# LCD_SCH.net
KiCad netlist of a schematic drawn in Altium Designer
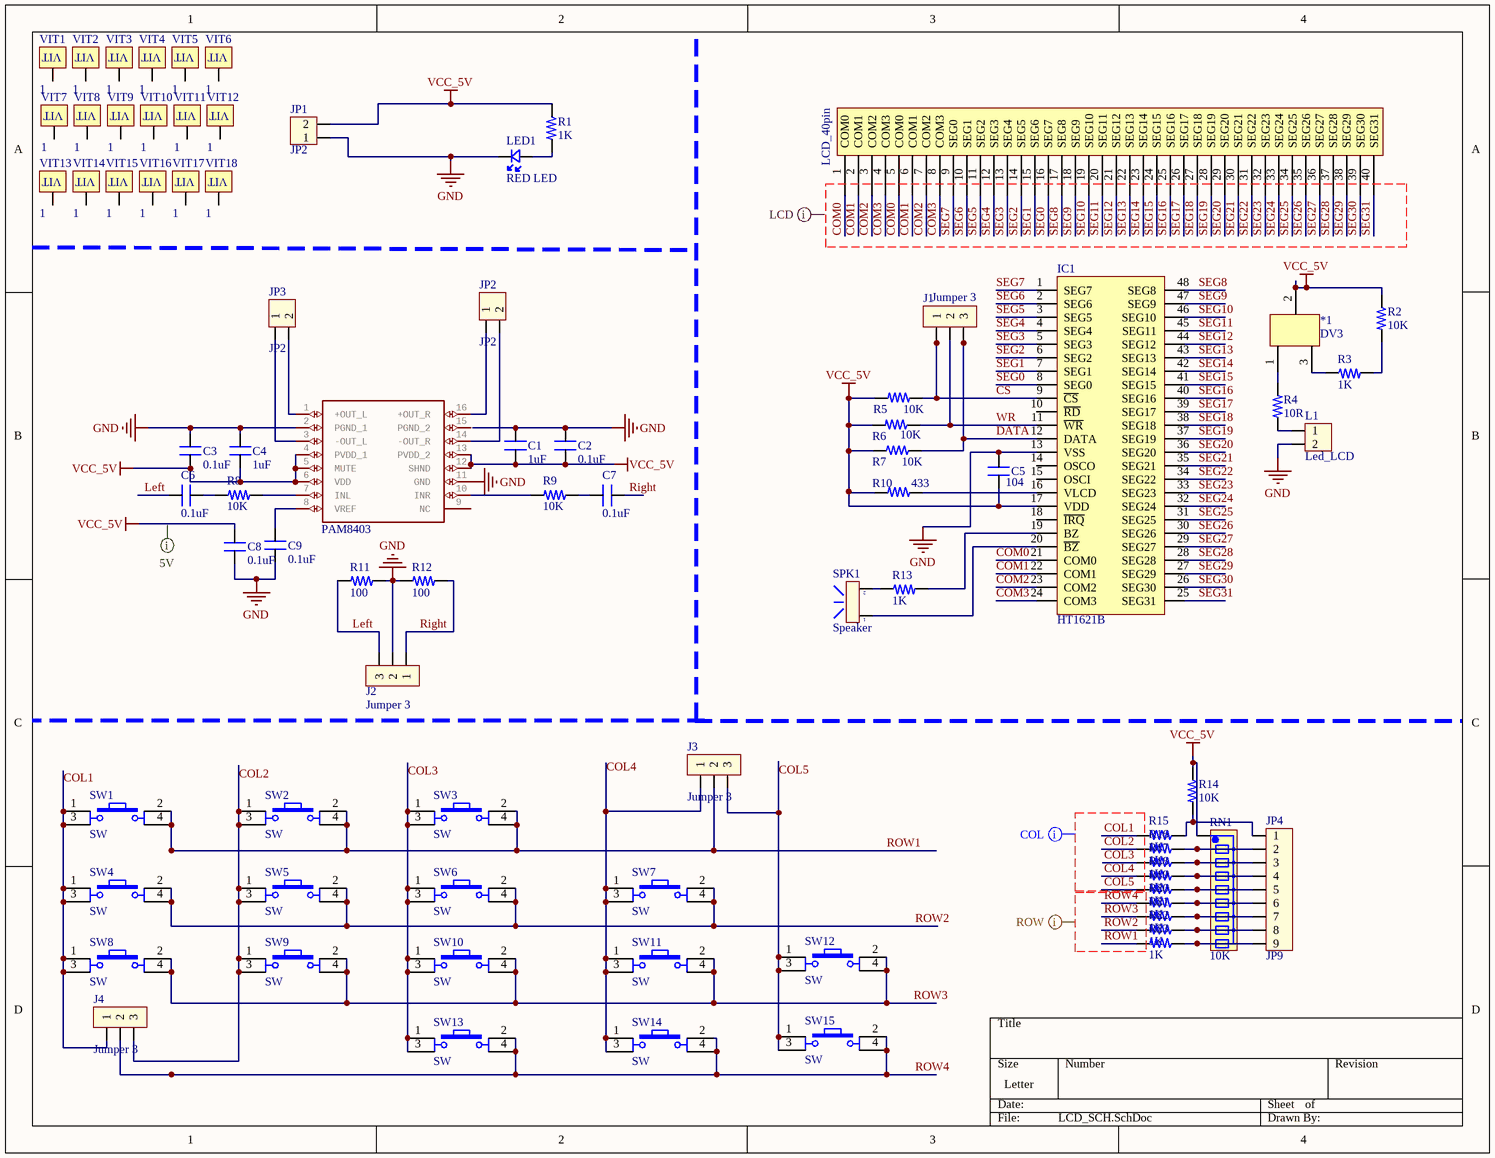
[diagram p0: LCD_SCH.SchDoc]

(export (version "E")
  (design (tool "Eeschema 10.0.6"))
  (components
    (comp (ref "*1") (value "DV3") (footprint "SOT23B") (libsource (lib "QD_Lib_Altum") (part "DV3")))
    (comp (ref "*2")
      (value "PAM8403")
      (footprint "PAM8403")
      (libsource (lib "QD_Lib_Altum") (part "PAM8403"))
    )
    (comp (ref "C1")
      (value "1uF")
      (footprint "CAP_0805")
      (description "1µF ±5% 50V Ceramic Capacitor X7R 0805 (2012 Metric)")
      (fields
        (field (name "MANUFACTURER") "Yageo")
        (field (name "MANUFACTURING PART NUMBER") "CC0805JKX7R9BB105")
      )
      (libsource (lib "QD_Lib_Altum") (part "CAP_1uF-50V-5%-0805"))
    )
    (comp (ref "C2")
      (value "0.1uF")
      (footprint "CAP_0805")
      (description "0.1µF ±5% 50V Ceramic Capacitor X7R 0805 (2012 Metric)")
      (fields
        (field (name "MANUFACTURER") "KEMET")
        (field (name "MANUFACTURING PART NUMBER") "C0805C104J5RACTU")
      )
      (libsource (lib "QD_Lib_Altum") (part "CAP_0.1uF-50V-5%-0805"))
    )
    (comp (ref "C3")
      (value "0.1uF")
      (footprint "CAP_0805")
      (description "0.1µF ±5% 50V Ceramic Capacitor X7R 0805 (2012 Metric)")
      (fields
        (field (name "MANUFACTURER") "KEMET")
        (field (name "MANUFACTURING PART NUMBER") "C0805C104J5RACTU")
      )
      (libsource (lib "QD_Lib_Altum") (part "CAP_0.1uF-50V-5%-0805"))
    )
    (comp (ref "C4")
      (value "1uF")
      (footprint "CAP_0805")
      (description "1µF ±5% 50V Ceramic Capacitor X7R 0805 (2012 Metric)")
      (fields
        (field (name "MANUFACTURER") "Yageo")
        (field (name "MANUFACTURING PART NUMBER") "CC0805JKX7R9BB105")
      )
      (libsource (lib "QD_Lib_Altum") (part "CAP_1uF-50V-5%-0805"))
    )
    (comp (ref "C5")
      (value "104")
      (footprint "CAP_0805")
      (description "0.1µF ±5% 50V Ceramic Capacitor X7R 0805 (2012 Metric)")
      (fields
        (field (name "MANUFACTURER") "KEMET")
        (field (name "MANUFACTURING PART NUMBER") "C0805C104J5RACTU")
      )
      (libsource (lib "QD_Lib_Altum") (part "CAP_0.1uF-50V-5%-0805"))
    )
    (comp (ref "C6")
      (value "0.1uF")
      (footprint "CAP_0805")
      (description "0.1µF ±5% 50V Ceramic Capacitor X7R 0805 (2012 Metric)")
      (fields
        (field (name "MANUFACTURER") "KEMET")
        (field (name "MANUFACTURING PART NUMBER") "C0805C104J5RACTU")
      )
      (libsource (lib "QD_Lib_Altum") (part "CAP_0.1uF-50V-5%-0805"))
    )
    (comp (ref "C7")
      (value "0.1uF")
      (footprint "CAP_0805")
      (description "0.1µF ±5% 50V Ceramic Capacitor X7R 0805 (2012 Metric)")
      (fields
        (field (name "MANUFACTURER") "KEMET")
        (field (name "MANUFACTURING PART NUMBER") "C0805C104J5RACTU")
      )
      (libsource (lib "QD_Lib_Altum") (part "CAP_0.1uF-50V-5%-0805"))
    )
    (comp (ref "C8")
      (value "0.1uF")
      (footprint "CAP_0805")
      (description "0.1µF ±5% 50V Ceramic Capacitor X7R 0805 (2012 Metric)")
      (fields
        (field (name "MANUFACTURER") "KEMET")
        (field (name "MANUFACTURING PART NUMBER") "C0805C104J5RACTU")
      )
      (libsource (lib "QD_Lib_Altum") (part "CAP_0.1uF-50V-5%-0805"))
    )
    (comp (ref "C9")
      (value "0.1uF")
      (footprint "CAP_0805")
      (description "0.1µF ±5% 50V Ceramic Capacitor X7R 0805 (2012 Metric)")
      (fields
        (field (name "MANUFACTURER") "KEMET")
        (field (name "MANUFACTURING PART NUMBER") "C0805C104J5RACTU")
      )
      (libsource (lib "QD_Lib_Altum") (part "CAP_0.1uF-50V-5%-0805"))
    )
    (comp (ref "IC1")
      (value "HT1621B")
      (footprint "HT1621")
      (description "5V - 256kHz - 1/4 Duty - 32X4 LCD - 3 Wire INTERFACE")
      (libsource (lib "QD_Lib_Altum") (part "HT1621B"))
    )
    (comp (ref "J1") (value "Jumper 3") (footprint "JP3") (libsource (lib "QD_Lib_Altum") (part "JP3")))
    (comp (ref "J2") (value "Jumper 3") (footprint "JP3") (libsource (lib "") (part "JP3_1")))
    (comp (ref "J3") (value "Jumper 3") (footprint "JP3") (libsource (lib "QD_Lib_Altum") (part "JP3")))
    (comp (ref "J4") (value "Jumper 3") (footprint "JP3") (libsource (lib "QD_Lib_Altum") (part "JP3")))
    (comp (ref "JP1")
      (value "JP2")
      (footprint "CON2")
      (description "Connector 2")
      (libsource (lib "QD_Lib_Altum") (part "Con2"))
    )
    (comp (ref "JP2")
      (value "JP2")
      (footprint "CON2")
      (description "Connector 2")
      (libsource (lib "") (part "Con2_1"))
    )
    (comp (ref "JP3")
      (value "JP2")
      (footprint "CON2")
      (description "Connector 2")
      (libsource (lib "") (part "Con2_1"))
    )
    (comp (ref "JP4")
      (value "JP9")
      (footprint "CON9")
      (description "Connector 9")
      (libsource (lib "QD_Lib_Altum") (part "Con9"))
    )
    (comp (ref "L1")
      (value "Led_LCD")
      (footprint "Led_LCD")
      (description "Led LCD 5V")
      (libsource (lib "QD_Lib_Altum") (part "Led_LCD"))
    )
    (comp (ref "LCD1")
      (value "LCD_40pin")
      (footprint "LCD_40P")
      (description "LCD_40Pin")
      (libsource (lib "QD_Lib_Altum") (part "LCD_40pin"))
    )
    (comp (ref "LED1")
      (value "RED LED")
      (footprint "LED_0805")
      (description "Red 621nm LED Indication - Discrete 2V 0805 (2012 Metric)")
      (fields
        (field (name "MANUFACTURER") "Lite-On Inc.")
        (field (name "MANUFACTURER PART NUMBER") "LTST-C170EKT")
      )
      (libsource (lib "QD_Lib_Altum") (part "LED-RED_10mA-0805"))
    )
    (comp (ref "R1")
      (value "1K")
      (footprint "RES_0805")
      (description "1 kOhms ±1% 0.125W, 1/8W Chip Resistor 0805 (2012 Metric) Moisture Resistant Thick Film")
      (fields (field (name "MANUFACTURER") "垈㎵á") (field (name "MANUFACTURER PART NUMBER") "RC0805FR-071KL"))
      (libsource (lib "QD_Lib_Altum") (part "RES_1K-0.125W-1%-0805"))
    )
    (comp (ref "R2")
      (value "10K")
      (footprint "RES_0805")
      (description "10 kOhms ±1% 0.125W, 1/8W Chip Resistor 0805 (2012 Metric) Moisture Resistant Thick Film")
      (fields
        (field (name "MANUFACTURER") "Yageo")
        (field (name "MANUFACTURING PART NUMBER") "RC0805FR-0710KL")
      )
      (libsource (lib "QD_Lib_Altum") (part "RES_10K-0.125W-1%-0805"))
    )
    (comp (ref "R3")
      (value "1K")
      (footprint "RES_0805")
      (description "1 kOhms ±1% 0.125W, 1/8W Chip Resistor 0805 (2012 Metric) Moisture Resistant Thick Film")
      (fields (field (name "MANUFACTURER") "垈㎵á") (field (name "MANUFACTURER PART NUMBER") "RC0805FR-071KL"))
      (libsource (lib "QD_Lib_Altum") (part "RES_1K-0.125W-1%-0805"))
    )
    (comp (ref "R4")
      (value "10R")
      (footprint "RES_0805")
      (fields (field (name "MANUFACTURER") "垈㎵á") (field (name "MANUFACTURER PART NUMBER") "RC0805FR-071KL"))
      (libsource (lib "QD_Lib_Altum") (part "RES_1K-0.125W-1%-0805"))
    )
    (comp (ref "R5")
      (value "10K")
      (footprint "RES_0805")
      (description "10 kOhms ±1% 0.125W, 1/8W Chip Resistor 0805 (2012 Metric) Moisture Resistant Thick Film")
      (fields
        (field (name "MANUFACTURER") "Yageo")
        (field (name "MANUFACTURING PART NUMBER") "RC0805FR-0710KL")
      )
      (libsource (lib "QD_Lib_Altum") (part "RES_10K-0.125W-1%-0805"))
    )
    (comp (ref "R6")
      (value "10K")
      (footprint "RES_0805")
      (description "10 kOhms ±1% 0.125W, 1/8W Chip Resistor 0805 (2012 Metric) Moisture Resistant Thick Film")
      (fields
        (field (name "MANUFACTURER") "Yageo")
        (field (name "MANUFACTURING PART NUMBER") "RC0805FR-0710KL")
      )
      (libsource (lib "QD_Lib_Altum") (part "RES_10K-0.125W-1%-0805"))
    )
    (comp (ref "R7")
      (value "10K")
      (footprint "RES_0805")
      (description "10 kOhms ±1% 0.125W, 1/8W Chip Resistor 0805 (2012 Metric) Moisture Resistant Thick Film")
      (fields
        (field (name "MANUFACTURER") "Yageo")
        (field (name "MANUFACTURING PART NUMBER") "RC0805FR-0710KL")
      )
      (libsource (lib "QD_Lib_Altum") (part "RES_10K-0.125W-1%-0805"))
    )
    (comp (ref "R8")
      (value "10K")
      (footprint "RES_0805")
      (description "10 kOhms ±1% 0.125W, 1/8W Chip Resistor 0805 (2012 Metric) Moisture Resistant Thick Film")
      (fields
        (field (name "MANUFACTURER") "Yageo")
        (field (name "MANUFACTURING PART NUMBER") "RC0805FR-0710KL")
      )
      (libsource (lib "QD_Lib_Altum") (part "RES_10K-0.125W-1%-0805"))
    )
    (comp (ref "R9")
      (value "10K")
      (footprint "RES_0805")
      (description "10 kOhms ±1% 0.125W, 1/8W Chip Resistor 0805 (2012 Metric) Moisture Resistant Thick Film")
      (fields
        (field (name "MANUFACTURER") "Yageo")
        (field (name "MANUFACTURING PART NUMBER") "RC0805FR-0710KL")
      )
      (libsource (lib "QD_Lib_Altum") (part "RES_10K-0.125W-1%-0805"))
    )
    (comp (ref "R10")
      (value "433")
      (footprint "RES_0805")
      (description "433 Ohms ±1% 0.125W, 1/8W Chip Resistor 0805 (2012 Metric) Moisture Resistant Thick Film")
      (fields
        (field (name "MANUFACTURER") "Yageo")
        (field (name "MANUFACTURING PART NUMBER") "RC0805FR-0710KL")
      )
      (libsource (lib "QD_Lib_Altum") (part "RES_10K-0.125W-1%-0805"))
    )
    (comp (ref "R11")
      (value "100")
      (footprint "RES_0805")
      (description "0Ohms ±1% 0.125W, 1/8W Chip Resistor 0805 (2012 Metric) Moisture Resistant Thick Film")
      (fields (field (name "MANUFACTURER") "垈㎵á") (field (name "MANUFACTURER PART NUMBER") "RC0805FR-071KL"))
      (libsource (lib "QD_Lib_Altum") (part "RES_0ohm-0.125W-1%-0805_1"))
    )
    (comp (ref "R12")
      (value "100")
      (footprint "RES_0805")
      (description "0Ohms ±1% 0.125W, 1/8W Chip Resistor 0805 (2012 Metric) Moisture Resistant Thick Film")
      (fields (field (name "MANUFACTURER") "垈㎵á") (field (name "MANUFACTURER PART NUMBER") "RC0805FR-071KL"))
      (libsource (lib "QD_Lib_Altum") (part "RES_0ohm-0.125W-1%-0805_1"))
    )
    (comp (ref "R13")
      (value "1K")
      (footprint "RES_0805")
      (description "1 kOhms ±1% 0.125W, 1/8W Chip Resistor 0805 (2012 Metric) Moisture Resistant Thick Film")
      (fields (field (name "MANUFACTURER") "垈㎵á") (field (name "MANUFACTURER PART NUMBER") "RC0805FR-071KL"))
      (libsource (lib "QD_Lib_Altum") (part "RES_1K-0.125W-1%-0805"))
    )
    (comp (ref "R14")
      (value "10K")
      (footprint "RES_0805")
      (description "10 kOhms ±1% 0.125W, 1/8W Chip Resistor 0805 (2012 Metric) Moisture Resistant Thick Film")
      (fields
        (field (name "MANUFACTURER") "Yageo")
        (field (name "MANUFACTURING PART NUMBER") "RC0805FR-0710KL")
      )
      (libsource (lib "QD_Lib_Altum") (part "RES_10K-0.125W-1%-0805"))
    )
    (comp (ref "R15")
      (value "1K")
      (footprint "RES_0805")
      (description "1 kOhms ±1% 0.125W, 1/8W Chip Resistor 0805 (2012 Metric) Moisture Resistant Thick Film")
      (fields (field (name "MANUFACTURER") "垈㎵á") (field (name "MANUFACTURER PART NUMBER") "RC0805FR-071KL"))
      (libsource (lib "QD_Lib_Altum") (part "RES_1K-0.125W-1%-0805"))
    )
    (comp (ref "R16")
      (value "1K")
      (footprint "RES_0805")
      (description "1 kOhms ±1% 0.125W, 1/8W Chip Resistor 0805 (2012 Metric) Moisture Resistant Thick Film")
      (fields (field (name "MANUFACTURER") "垈㎵á") (field (name "MANUFACTURER PART NUMBER") "RC0805FR-071KL"))
      (libsource (lib "QD_Lib_Altum") (part "RES_1K-0.125W-1%-0805"))
    )
    (comp (ref "R17")
      (value "1K")
      (footprint "RES_0805")
      (description "1 kOhms ±1% 0.125W, 1/8W Chip Resistor 0805 (2012 Metric) Moisture Resistant Thick Film")
      (fields (field (name "MANUFACTURER") "垈㎵á") (field (name "MANUFACTURER PART NUMBER") "RC0805FR-071KL"))
      (libsource (lib "QD_Lib_Altum") (part "RES_1K-0.125W-1%-0805"))
    )
    (comp (ref "R18")
      (value "1K")
      (footprint "RES_0805")
      (description "1 kOhms ±1% 0.125W, 1/8W Chip Resistor 0805 (2012 Metric) Moisture Resistant Thick Film")
      (fields (field (name "MANUFACTURER") "垈㎵á") (field (name "MANUFACTURER PART NUMBER") "RC0805FR-071KL"))
      (libsource (lib "QD_Lib_Altum") (part "RES_1K-0.125W-1%-0805"))
    )
    (comp (ref "R19")
      (value "1K")
      (footprint "RES_0805")
      (description "1 kOhms ±1% 0.125W, 1/8W Chip Resistor 0805 (2012 Metric) Moisture Resistant Thick Film")
      (fields (field (name "MANUFACTURER") "垈㎵á") (field (name "MANUFACTURER PART NUMBER") "RC0805FR-071KL"))
      (libsource (lib "QD_Lib_Altum") (part "RES_1K-0.125W-1%-0805"))
    )
    (comp (ref "R20")
      (value "1K")
      (footprint "RES_0805")
      (description "1 kOhms ±1% 0.125W, 1/8W Chip Resistor 0805 (2012 Metric) Moisture Resistant Thick Film")
      (fields (field (name "MANUFACTURER") "垈㎵á") (field (name "MANUFACTURER PART NUMBER") "RC0805FR-071KL"))
      (libsource (lib "QD_Lib_Altum") (part "RES_1K-0.125W-1%-0805"))
    )
    (comp (ref "R21")
      (value "1K")
      (footprint "RES_0805")
      (description "1 kOhms ±1% 0.125W, 1/8W Chip Resistor 0805 (2012 Metric) Moisture Resistant Thick Film")
      (fields (field (name "MANUFACTURER") "垈㎵á") (field (name "MANUFACTURER PART NUMBER") "RC0805FR-071KL"))
      (libsource (lib "QD_Lib_Altum") (part "RES_1K-0.125W-1%-0805"))
    )
    (comp (ref "R22")
      (value "1K")
      (footprint "RES_0805")
      (description "1 kOhms ±1% 0.125W, 1/8W Chip Resistor 0805 (2012 Metric) Moisture Resistant Thick Film")
      (fields (field (name "MANUFACTURER") "垈㎵á") (field (name "MANUFACTURER PART NUMBER") "RC0805FR-071KL"))
      (libsource (lib "QD_Lib_Altum") (part "RES_1K-0.125W-1%-0805"))
    )
    (comp (ref "R23")
      (value "1K")
      (footprint "RES_0805")
      (description "1 kOhms ±1% 0.125W, 1/8W Chip Resistor 0805 (2012 Metric) Moisture Resistant Thick Film")
      (fields (field (name "MANUFACTURER") "垈㎵á") (field (name "MANUFACTURER PART NUMBER") "RC0805FR-071KL"))
      (libsource (lib "QD_Lib_Altum") (part "RES_1K-0.125W-1%-0805"))
    )
    (comp (ref "RN1")
      (value "10K")
      (footprint "RN8")
      (description "Resistor 8 (Thanh)")
      (libsource (lib "QD_Lib_Altum") (part "RN8"))
    )
    (comp (ref "SPK1")
      (value "Speaker")
      (footprint "SPK1")
      (description "Speaker Chip")
      (libsource (lib "QD_Lib_Altum") (part "SPK1"))
    )
    (comp (ref "SW1")
      (value "SW")
      (footprint "SW4_1012")
      (description "Switch button 4 pin")
      (libsource (lib "QD_Lib_Altum") (part "SW4"))
    )
    (comp (ref "SW2")
      (value "SW")
      (footprint "SW4_1012")
      (description "Switch button 4 pin")
      (libsource (lib "QD_Lib_Altum") (part "SW4"))
    )
    (comp (ref "SW3")
      (value "SW")
      (footprint "SW4_1012")
      (description "Switch button 4 pin")
      (libsource (lib "QD_Lib_Altum") (part "SW4"))
    )
    (comp (ref "SW4")
      (value "SW")
      (footprint "SW4_1012")
      (description "Switch button 4 pin")
      (libsource (lib "QD_Lib_Altum") (part "SW4"))
    )
    (comp (ref "SW5")
      (value "SW")
      (footprint "SW4_1012")
      (description "Switch button 4 pin")
      (libsource (lib "QD_Lib_Altum") (part "SW4"))
    )
    (comp (ref "SW6")
      (value "SW")
      (footprint "SW4_1012")
      (description "Switch button 4 pin")
      (libsource (lib "QD_Lib_Altum") (part "SW4"))
    )
    (comp (ref "SW7")
      (value "SW")
      (footprint "SW4_1012")
      (description "Switch button 4 pin")
      (libsource (lib "QD_Lib_Altum") (part "SW4"))
    )
    (comp (ref "SW8")
      (value "SW")
      (footprint "SW4_1012")
      (description "Switch button 4 pin")
      (libsource (lib "QD_Lib_Altum") (part "SW4"))
    )
    (comp (ref "SW9")
      (value "SW")
      (footprint "SW4_1012")
      (description "Switch button 4 pin")
      (libsource (lib "QD_Lib_Altum") (part "SW4"))
    )
    (comp (ref "SW10")
      (value "SW")
      (footprint "SW4_1012")
      (description "Switch button 4 pin")
      (libsource (lib "QD_Lib_Altum") (part "SW4"))
    )
    (comp (ref "SW11")
      (value "SW")
      (footprint "SW4_1012")
      (description "Switch button 4 pin")
      (libsource (lib "QD_Lib_Altum") (part "SW4"))
    )
    (comp (ref "SW12")
      (value "SW")
      (footprint "SW4_1012")
      (description "Switch button 4 pin")
      (libsource (lib "QD_Lib_Altum") (part "SW4"))
    )
    (comp (ref "SW13")
      (value "SW")
      (footprint "SW4_1012")
      (description "Switch button 4 pin")
      (libsource (lib "QD_Lib_Altum") (part "SW4"))
    )
    (comp (ref "SW14")
      (value "SW")
      (footprint "SW4_1012")
      (description "Switch button 4 pin")
      (libsource (lib "QD_Lib_Altum") (part "SW4"))
    )
    (comp (ref "SW15")
      (value "SW")
      (footprint "SW4_1012")
      (description "Switch button 4 pin")
      (libsource (lib "QD_Lib_Altum") (part "SW4"))
    )
    (comp (ref "VIT1")
      (value "1")
      (footprint "VIT")
      (description "Oc Vit")
      (libsource (lib "QD_Lib_Altum") (part "VIT"))
    )
    (comp (ref "VIT2")
      (value "1")
      (footprint "VIT")
      (description "Oc Vit")
      (libsource (lib "QD_Lib_Altum") (part "VIT"))
    )
    (comp (ref "VIT3")
      (value "1")
      (footprint "VIT")
      (description "Oc Vit")
      (libsource (lib "QD_Lib_Altum") (part "VIT"))
    )
    (comp (ref "VIT4")
      (value "1")
      (footprint "VIT")
      (description "Oc Vit")
      (libsource (lib "QD_Lib_Altum") (part "VIT"))
    )
    (comp (ref "VIT5")
      (value "1")
      (footprint "VIT")
      (description "Oc Vit")
      (libsource (lib "QD_Lib_Altum") (part "VIT"))
    )
    (comp (ref "VIT6")
      (value "1")
      (footprint "VIT")
      (description "Oc Vit")
      (libsource (lib "QD_Lib_Altum") (part "VIT"))
    )
    (comp (ref "VIT7")
      (value "1")
      (footprint "VIT")
      (description "Oc Vit")
      (libsource (lib "QD_Lib_Altum") (part "VIT"))
    )
    (comp (ref "VIT8")
      (value "1")
      (footprint "VIT")
      (description "Oc Vit")
      (libsource (lib "QD_Lib_Altum") (part "VIT"))
    )
    (comp (ref "VIT9")
      (value "1")
      (footprint "VIT")
      (description "Oc Vit")
      (libsource (lib "QD_Lib_Altum") (part "VIT"))
    )
    (comp (ref "VIT10")
      (value "1")
      (footprint "VIT")
      (description "Oc Vit")
      (libsource (lib "QD_Lib_Altum") (part "VIT"))
    )
    (comp (ref "VIT11")
      (value "1")
      (footprint "VIT")
      (description "Oc Vit")
      (libsource (lib "QD_Lib_Altum") (part "VIT"))
    )
    (comp (ref "VIT12")
      (value "1")
      (footprint "VIT")
      (description "Oc Vit")
      (libsource (lib "QD_Lib_Altum") (part "VIT"))
    )
    (comp (ref "VIT13")
      (value "1")
      (footprint "VIT")
      (description "Oc Vit")
      (libsource (lib "QD_Lib_Altum") (part "VIT"))
    )
    (comp (ref "VIT14")
      (value "1")
      (footprint "VIT")
      (description "Oc Vit")
      (libsource (lib "QD_Lib_Altum") (part "VIT"))
    )
    (comp (ref "VIT15")
      (value "1")
      (footprint "VIT")
      (description "Oc Vit")
      (libsource (lib "QD_Lib_Altum") (part "VIT"))
    )
    (comp (ref "VIT16")
      (value "1")
      (footprint "VIT")
      (description "Oc Vit")
      (libsource (lib "QD_Lib_Altum") (part "VIT"))
    )
    (comp (ref "VIT17")
      (value "1")
      (footprint "VIT")
      (description "Oc Vit")
      (libsource (lib "QD_Lib_Altum") (part "VIT"))
    )
    (comp (ref "VIT18")
      (value "1")
      (footprint "VIT")
      (description "Oc Vit")
      (libsource (lib "QD_Lib_Altum") (part "VIT"))
    )
  )
  (nets
    (net (code "1") (name "/COL1") (class "Default")
      (node (ref "J4") (pin "1") (pinfunction "1_1") (pintype "passive"))
      (node (ref "R15") (pin "1") (pinfunction "1_1") (pintype "passive"))
      (node (ref "SW1") (pin "1") (pintype "passive"))
      (node (ref "SW1") (pin "3") (pintype "passive"))
      (node (ref "SW4") (pin "1") (pintype "passive"))
      (node (ref "SW4") (pin "3") (pintype "passive"))
      (node (ref "SW8") (pin "1") (pintype "passive"))
      (node (ref "SW8") (pin "3") (pintype "passive"))
    )
    (net (code "2") (name "/COL2") (class "Default")
      (node (ref "J4") (pin "3") (pinfunction "3_3") (pintype "passive"))
      (node (ref "R16") (pin "1") (pinfunction "1_1") (pintype "passive"))
      (node (ref "SW2") (pin "1") (pintype "passive"))
      (node (ref "SW2") (pin "3") (pintype "passive"))
      (node (ref "SW5") (pin "1") (pintype "passive"))
      (node (ref "SW5") (pin "3") (pintype "passive"))
      (node (ref "SW9") (pin "1") (pintype "passive"))
      (node (ref "SW9") (pin "3") (pintype "passive"))
    )
    (net (code "3") (name "/COL3") (class "Default")
      (node (ref "R17") (pin "1") (pinfunction "1_1") (pintype "passive"))
      (node (ref "SW10") (pin "1") (pintype "passive"))
      (node (ref "SW10") (pin "3") (pintype "passive"))
      (node (ref "SW13") (pin "1") (pintype "passive"))
      (node (ref "SW13") (pin "3") (pintype "passive"))
      (node (ref "SW3") (pin "1") (pintype "passive"))
      (node (ref "SW3") (pin "3") (pintype "passive"))
      (node (ref "SW6") (pin "1") (pintype "passive"))
      (node (ref "SW6") (pin "3") (pintype "passive"))
    )
    (net (code "4") (name "/COL4") (class "Default")
      (node (ref "J3") (pin "1") (pinfunction "1_1") (pintype "passive"))
      (node (ref "R18") (pin "1") (pinfunction "1_1") (pintype "passive"))
      (node (ref "SW11") (pin "1") (pintype "passive"))
      (node (ref "SW11") (pin "3") (pintype "passive"))
      (node (ref "SW14") (pin "1") (pintype "passive"))
      (node (ref "SW14") (pin "3") (pintype "passive"))
      (node (ref "SW7") (pin "1") (pintype "passive"))
      (node (ref "SW7") (pin "3") (pintype "passive"))
    )
    (net (code "5") (name "/COL5") (class "Default")
      (node (ref "J3") (pin "3") (pinfunction "3_3") (pintype "passive"))
      (node (ref "R19") (pin "1") (pinfunction "1_1") (pintype "passive"))
      (node (ref "SW12") (pin "1") (pintype "passive"))
      (node (ref "SW12") (pin "3") (pintype "passive"))
      (node (ref "SW15") (pin "1") (pintype "passive"))
      (node (ref "SW15") (pin "3") (pintype "passive"))
    )
    (net (code "6") (name "/COM0") (class "Default")
      (node (ref "IC1") (pin "21") (pinfunction "COM0_21") (pintype "passive"))
      (node (ref "LCD1") (pin "1") (pinfunction "COM0_1") (pintype "passive"))
      (node (ref "LCD1") (pin "5") (pinfunction "COM0_5") (pintype "passive"))
    )
    (net (code "7") (name "/COM1") (class "Default")
      (node (ref "IC1") (pin "22") (pinfunction "COM1_22") (pintype "passive"))
      (node (ref "LCD1") (pin "2") (pinfunction "COM1_2") (pintype "passive"))
      (node (ref "LCD1") (pin "6") (pinfunction "COM1_6") (pintype "passive"))
    )
    (net (code "8") (name "/COM2") (class "Default")
      (node (ref "IC1") (pin "23") (pinfunction "COM2_23") (pintype "passive"))
      (node (ref "LCD1") (pin "3") (pinfunction "COM2_3") (pintype "passive"))
      (node (ref "LCD1") (pin "7") (pinfunction "COM2_7") (pintype "passive"))
    )
    (net (code "9") (name "/COM3") (class "Default")
      (node (ref "IC1") (pin "24") (pinfunction "COM3_24") (pintype "passive"))
      (node (ref "LCD1") (pin "4") (pinfunction "COM3_4") (pintype "passive"))
      (node (ref "LCD1") (pin "8") (pinfunction "COM3_8") (pintype "passive"))
    )
    (net (code "10") (name "/CS") (class "Default")
      (node (ref "IC1") (pin "9") (pinfunction "~{CS}_9") (pintype "passive"))
      (node (ref "J1") (pin "1") (pinfunction "1_1") (pintype "passive"))
      (node (ref "R5") (pin "2") (pinfunction "2_2") (pintype "passive"))
    )
    (net (code "11") (name "/DATA") (class "Default")
      (node (ref "IC1") (pin "12") (pinfunction "DATA_12") (pintype "passive"))
      (node (ref "J1") (pin "3") (pinfunction "3_3") (pintype "passive"))
      (node (ref "R7") (pin "2") (pinfunction "2_2") (pintype "passive"))
    )
    (net (code "12") (name "/Left") (class "Default")
      (node (ref "C6") (pin "2") (pinfunction "2_2") (pintype "passive"))
      (node (ref "J2") (pin "3") (pinfunction "3_3") (pintype "passive"))
      (node (ref "R11") (pin "2") (pinfunction "2_2") (pintype "passive"))
    )
    (net (code "13") (name "/ROW1") (class "Default")
      (node (ref "J3") (pin "2") (pinfunction "2_2") (pintype "passive"))
      (node (ref "R23") (pin "1") (pinfunction "1_1") (pintype "passive"))
      (node (ref "SW1") (pin "2") (pintype "passive"))
      (node (ref "SW1") (pin "4") (pintype "passive"))
      (node (ref "SW2") (pin "2") (pintype "passive"))
      (node (ref "SW2") (pin "4") (pintype "passive"))
      (node (ref "SW3") (pin "2") (pintype "passive"))
      (node (ref "SW3") (pin "4") (pintype "passive"))
    )
    (net (code "14") (name "/ROW2") (class "Default")
      (node (ref "R22") (pin "1") (pinfunction "1_1") (pintype "passive"))
      (node (ref "SW4") (pin "2") (pintype "passive"))
      (node (ref "SW4") (pin "4") (pintype "passive"))
      (node (ref "SW5") (pin "2") (pintype "passive"))
      (node (ref "SW5") (pin "4") (pintype "passive"))
      (node (ref "SW6") (pin "2") (pintype "passive"))
      (node (ref "SW6") (pin "4") (pintype "passive"))
      (node (ref "SW7") (pin "2") (pintype "passive"))
      (node (ref "SW7") (pin "4") (pintype "passive"))
    )
    (net (code "15") (name "/ROW3") (class "Default")
      (node (ref "R21") (pin "1") (pinfunction "1_1") (pintype "passive"))
      (node (ref "SW10") (pin "2") (pintype "passive"))
      (node (ref "SW10") (pin "4") (pintype "passive"))
      (node (ref "SW11") (pin "2") (pintype "passive"))
      (node (ref "SW11") (pin "4") (pintype "passive"))
      (node (ref "SW12") (pin "2") (pintype "passive"))
      (node (ref "SW12") (pin "4") (pintype "passive"))
      (node (ref "SW8") (pin "2") (pintype "passive"))
      (node (ref "SW8") (pin "4") (pintype "passive"))
      (node (ref "SW9") (pin "2") (pintype "passive"))
      (node (ref "SW9") (pin "4") (pintype "passive"))
    )
    (net (code "16") (name "/ROW4") (class "Default")
      (node (ref "J4") (pin "2") (pinfunction "2_2") (pintype "passive"))
      (node (ref "R20") (pin "1") (pinfunction "1_1") (pintype "passive"))
      (node (ref "SW13") (pin "2") (pintype "passive"))
      (node (ref "SW13") (pin "4") (pintype "passive"))
      (node (ref "SW14") (pin "2") (pintype "passive"))
      (node (ref "SW14") (pin "4") (pintype "passive"))
      (node (ref "SW15") (pin "2") (pintype "passive"))
      (node (ref "SW15") (pin "4") (pintype "passive"))
    )
    (net (code "17") (name "/Right") (class "Default")
      (node (ref "C7") (pin "1") (pinfunction "1_1") (pintype "passive"))
      (node (ref "J2") (pin "1") (pinfunction "1_1") (pintype "passive"))
      (node (ref "R12") (pin "1") (pinfunction "1_1") (pintype "passive"))
    )
    (net (code "18") (name "/SEG0") (class "Default")
      (node (ref "IC1") (pin "8") (pinfunction "SEG0_8") (pintype "passive"))
      (node (ref "LCD1") (pin "16") (pinfunction "SEG7_16") (pintype "passive"))
    )
    (net (code "19") (name "/SEG1") (class "Default")
      (node (ref "IC1") (pin "7") (pinfunction "SEG1_7") (pintype "passive"))
      (node (ref "LCD1") (pin "15") (pinfunction "SEG6_15") (pintype "passive"))
    )
    (net (code "20") (name "/SEG2") (class "Default")
      (node (ref "IC1") (pin "6") (pinfunction "SEG2_6") (pintype "passive"))
      (node (ref "LCD1") (pin "14") (pinfunction "SEG5_14") (pintype "passive"))
    )
    (net (code "21") (name "/SEG3") (class "Default")
      (node (ref "IC1") (pin "5") (pinfunction "SEG3_5") (pintype "passive"))
      (node (ref "LCD1") (pin "13") (pinfunction "SEG4_13") (pintype "passive"))
    )
    (net (code "22") (name "/SEG4") (class "Default")
      (node (ref "IC1") (pin "4") (pinfunction "SEG4_4") (pintype "passive"))
      (node (ref "LCD1") (pin "12") (pinfunction "SEG3_12") (pintype "passive"))
    )
    (net (code "23") (name "/SEG5") (class "Default")
      (node (ref "IC1") (pin "3") (pinfunction "SEG5_3") (pintype "passive"))
      (node (ref "LCD1") (pin "11") (pinfunction "SEG2_11") (pintype "passive"))
    )
    (net (code "24") (name "/SEG6") (class "Default")
      (node (ref "IC1") (pin "2") (pinfunction "SEG6_2") (pintype "passive"))
      (node (ref "LCD1") (pin "10") (pinfunction "SEG1_10") (pintype "passive"))
    )
    (net (code "25") (name "/SEG7") (class "Default")
      (node (ref "IC1") (pin "1") (pinfunction "SEG7_1") (pintype "passive"))
      (node (ref "LCD1") (pin "9") (pinfunction "SEG0_9") (pintype "passive"))
    )
    (net (code "26") (name "/SEG8") (class "Default")
      (node (ref "IC1") (pin "48") (pinfunction "SEG8_48") (pintype "passive"))
      (node (ref "LCD1") (pin "17") (pinfunction "SEG8_17") (pintype "passive"))
    )
    (net (code "27") (name "/SEG9") (class "Default")
      (node (ref "IC1") (pin "47") (pinfunction "SEG9_47") (pintype "passive"))
      (node (ref "LCD1") (pin "18") (pinfunction "SEG9_18") (pintype "passive"))
    )
    (net (code "28") (name "/SEG10") (class "Default")
      (node (ref "IC1") (pin "46") (pinfunction "SEG10_46") (pintype "passive"))
      (node (ref "LCD1") (pin "19") (pinfunction "SEG10_19") (pintype "passive"))
    )
    (net (code "29") (name "/SEG11") (class "Default")
      (node (ref "IC1") (pin "45") (pinfunction "SEG11_45") (pintype "passive"))
      (node (ref "LCD1") (pin "20") (pinfunction "SEG11_20") (pintype "passive"))
    )
    (net (code "30") (name "/SEG12") (class "Default")
      (node (ref "IC1") (pin "44") (pinfunction "SEG12_44") (pintype "passive"))
      (node (ref "LCD1") (pin "21") (pinfunction "SEG12_21") (pintype "passive"))
    )
    (net (code "31") (name "/SEG13") (class "Default")
      (node (ref "IC1") (pin "43") (pinfunction "SEG13_43") (pintype "passive"))
      (node (ref "LCD1") (pin "22") (pinfunction "SEG13_22") (pintype "passive"))
    )
    (net (code "32") (name "/SEG14") (class "Default")
      (node (ref "IC1") (pin "42") (pinfunction "SEG14_42") (pintype "passive"))
      (node (ref "LCD1") (pin "23") (pinfunction "SEG14_23") (pintype "passive"))
    )
    (net (code "33") (name "/SEG15") (class "Default")
      (node (ref "IC1") (pin "41") (pinfunction "SEG15_41") (pintype "passive"))
      (node (ref "LCD1") (pin "24") (pinfunction "SEG15_24") (pintype "passive"))
    )
    (net (code "34") (name "/SEG16") (class "Default")
      (node (ref "IC1") (pin "40") (pinfunction "SEG16_40") (pintype "passive"))
      (node (ref "LCD1") (pin "25") (pinfunction "SEG16_25") (pintype "passive"))
    )
    (net (code "35") (name "/SEG17") (class "Default")
      (node (ref "IC1") (pin "39") (pinfunction "SEG17_39") (pintype "passive"))
      (node (ref "LCD1") (pin "26") (pinfunction "SEG17_26") (pintype "passive"))
    )
    (net (code "36") (name "/SEG18") (class "Default")
      (node (ref "IC1") (pin "38") (pinfunction "SEG18_38") (pintype "passive"))
      (node (ref "LCD1") (pin "27") (pinfunction "SEG18_27") (pintype "passive"))
    )
    (net (code "37") (name "/SEG19") (class "Default")
      (node (ref "IC1") (pin "37") (pinfunction "SEG19_37") (pintype "passive"))
      (node (ref "LCD1") (pin "28") (pinfunction "SEG19_28") (pintype "passive"))
    )
    (net (code "38") (name "/SEG20") (class "Default")
      (node (ref "IC1") (pin "36") (pinfunction "SEG20_36") (pintype "passive"))
      (node (ref "LCD1") (pin "29") (pinfunction "SEG20_29") (pintype "passive"))
    )
    (net (code "39") (name "/SEG21") (class "Default")
      (node (ref "IC1") (pin "35") (pinfunction "SEG21_35") (pintype "passive"))
      (node (ref "LCD1") (pin "30") (pinfunction "SEG21_30") (pintype "passive"))
    )
    (net (code "40") (name "/SEG22") (class "Default")
      (node (ref "IC1") (pin "34") (pinfunction "SEG22_34") (pintype "passive"))
      (node (ref "LCD1") (pin "31") (pinfunction "SEG22_31") (pintype "passive"))
    )
    (net (code "41") (name "/SEG23") (class "Default")
      (node (ref "IC1") (pin "33") (pinfunction "SEG23_33") (pintype "passive"))
      (node (ref "LCD1") (pin "32") (pinfunction "SEG23_32") (pintype "passive"))
    )
    (net (code "42") (name "/SEG24") (class "Default")
      (node (ref "IC1") (pin "32") (pinfunction "SEG24_32") (pintype "passive"))
      (node (ref "LCD1") (pin "33") (pinfunction "SEG24_33") (pintype "passive"))
    )
    (net (code "43") (name "/SEG25") (class "Default")
      (node (ref "IC1") (pin "31") (pinfunction "SEG25_31") (pintype "passive"))
      (node (ref "LCD1") (pin "34") (pinfunction "SEG25_34") (pintype "passive"))
    )
    (net (code "44") (name "/SEG26") (class "Default")
      (node (ref "IC1") (pin "30") (pinfunction "SEG26_30") (pintype "passive"))
      (node (ref "LCD1") (pin "35") (pinfunction "SEG26_35") (pintype "passive"))
    )
    (net (code "45") (name "/SEG27") (class "Default")
      (node (ref "IC1") (pin "29") (pinfunction "SEG27_29") (pintype "passive"))
      (node (ref "LCD1") (pin "36") (pinfunction "SEG27_36") (pintype "passive"))
    )
    (net (code "46") (name "/SEG28") (class "Default")
      (node (ref "IC1") (pin "28") (pinfunction "SEG28_28") (pintype "passive"))
      (node (ref "LCD1") (pin "37") (pinfunction "SEG28_37") (pintype "passive"))
    )
    (net (code "47") (name "/SEG29") (class "Default")
      (node (ref "IC1") (pin "27") (pinfunction "SEG29_27") (pintype "passive"))
      (node (ref "LCD1") (pin "38") (pinfunction "SEG29_38") (pintype "passive"))
    )
    (net (code "48") (name "/SEG30") (class "Default")
      (node (ref "IC1") (pin "26") (pinfunction "SEG30_26") (pintype "passive"))
      (node (ref "LCD1") (pin "39") (pinfunction "SEG30_39") (pintype "passive"))
    )
    (net (code "49") (name "/SEG31") (class "Default")
      (node (ref "IC1") (pin "25") (pinfunction "SEG31_25") (pintype "passive"))
      (node (ref "LCD1") (pin "40") (pinfunction "SEG31_40") (pintype "passive"))
    )
    (net (code "50") (name "/WR") (class "Default")
      (node (ref "IC1") (pin "11") (pinfunction "~{WR}_11") (pintype "passive"))
      (node (ref "J1") (pin "2") (pinfunction "2_2") (pintype "passive"))
      (node (ref "R6") (pin "2") (pinfunction "2_2") (pintype "passive"))
    )
    (net (code "51") (name "GND") (class "Default")
      (node (ref "*2") (pin "11") (pinfunction "GND_11") (pintype "bidirectional"))
      (node (ref "*2") (pin "2") (pinfunction "PGND_1_2") (pintype "bidirectional"))
      (node (ref "C1") (pin "1") (pinfunction "1_1") (pintype "passive"))
      (node (ref "C2") (pin "1") (pinfunction "1_1") (pintype "passive"))
      (node (ref "C3") (pin "2") (pinfunction "2_2") (pintype "passive"))
      (node (ref "C4") (pin "2") (pinfunction "2_2") (pintype "passive"))
      (node (ref "C5") (pin "2") (pinfunction "2_2") (pintype "passive"))
      (node (ref "C8") (pin "2") (pinfunction "2_2") (pintype "passive"))
      (node (ref "C9") (pin "2") (pinfunction "2_2") (pintype "passive"))
      (node (ref "IC1") (pin "13") (pinfunction "VSS_13") (pintype "passive"))
      (node (ref "J2") (pin "2") (pinfunction "2_2") (pintype "passive"))
      (node (ref "JP1") (pin "1") (pinfunction "1_1") (pintype "passive"))
      (node (ref "L1") (pin "2") (pinfunction "2_2") (pintype "passive"))
      (node (ref "LED1") (pin "K") (pinfunction "K_K") (pintype "passive"))
      (node (ref "R11") (pin "1") (pinfunction "1_1") (pintype "passive"))
      (node (ref "R12") (pin "2") (pinfunction "2_2") (pintype "passive"))
    )
    (net (code "52") (name "Net-(*1-Pad1)") (class "Default")
      (node (ref "*1") (pin "1") (pintype "passive"))
      (node (ref "R4") (pin "2") (pinfunction "2_2") (pintype "passive"))
    )
    (net (code "53") (name "Net-(*1-Pad3)") (class "Default")
      (node (ref "*1") (pin "3") (pintype "passive"))
      (node (ref "R3") (pin "2") (pinfunction "2_2") (pintype "passive"))
    )
    (net (code "54") (name "Net-(*2-+OUT_L)") (class "Default")
      (node (ref "*2") (pin "1") (pinfunction "+OUT_L_1") (pintype "bidirectional"))
      (node (ref "JP3") (pin "2") (pinfunction "2_2") (pintype "passive"))
    )
    (net (code "55") (name "Net-(*2-+OUT_R)") (class "Default")
      (node (ref "*2") (pin "16") (pinfunction "+OUT_R_16") (pintype "bidirectional"))
      (node (ref "JP2") (pin "1") (pinfunction "1_1") (pintype "passive"))
    )
    (net (code "56") (name "Net-(*2--OUT_L)") (class "Default")
      (node (ref "*2") (pin "3") (pinfunction "-OUT_L_3") (pintype "bidirectional"))
      (node (ref "JP3") (pin "1") (pinfunction "1_1") (pintype "passive"))
    )
    (net (code "57") (name "Net-(*2--OUT_R)") (class "Default")
      (node (ref "*2") (pin "14") (pinfunction "-OUT_R_14") (pintype "bidirectional"))
      (node (ref "JP2") (pin "2") (pinfunction "2_2") (pintype "passive"))
    )
    (net (code "58") (name "Net-(*2-INL)") (class "Default")
      (node (ref "*2") (pin "7") (pinfunction "INL_7") (pintype "bidirectional"))
      (node (ref "R8") (pin "2") (pinfunction "2_2") (pintype "passive"))
    )
    (net (code "59") (name "Net-(*2-INR)") (class "Default")
      (node (ref "*2") (pin "10") (pinfunction "INR_10") (pintype "bidirectional"))
      (node (ref "R9") (pin "1") (pinfunction "1_1") (pintype "passive"))
    )
    (net (code "60") (name "Net-(*2-VREF)") (class "Default")
      (node (ref "*2") (pin "8") (pinfunction "VREF_8") (pintype "bidirectional"))
      (node (ref "C9") (pin "1") (pinfunction "1_1") (pintype "passive"))
    )
    (net (code "61") (name "Net-(C6-Pad1)") (class "Default")
      (node (ref "C6") (pin "1") (pinfunction "1_1") (pintype "passive"))
      (node (ref "R8") (pin "1") (pinfunction "1_1") (pintype "passive"))
    )
    (net (code "62") (name "Net-(C7-Pad2)") (class "Default")
      (node (ref "C7") (pin "2") (pinfunction "2_2") (pintype "passive"))
      (node (ref "R9") (pin "2") (pinfunction "2_2") (pintype "passive"))
    )
    (net (code "63") (name "Net-(IC1-BZ)") (class "Default")
      (node (ref "IC1") (pin "19") (pinfunction "BZ_19") (pintype "passive"))
      (node (ref "R13") (pin "1") (pinfunction "1_1") (pintype "passive"))
    )
    (net (code "64") (name "Net-(IC1-VLCD)") (class "Default")
      (node (ref "IC1") (pin "16") (pinfunction "VLCD_16") (pintype "passive"))
      (node (ref "R10") (pin "2") (pinfunction "2_2") (pintype "passive"))
    )
    (net (code "65") (name "Net-(IC1-~{BZ})") (class "Default")
      (node (ref "IC1") (pin "20") (pinfunction "~{BZ}_20") (pintype "passive"))
      (node (ref "SPK1") (pin "1") (pinfunction "1_1") (pintype "passive"))
    )
    (net (code "66") (name "Net-(JP4-Pad1)") (class "Default")
      (node (ref "JP4") (pin "1") (pinfunction "1_1") (pintype "passive"))
      (node (ref "R14") (pin "1") (pinfunction "1_1") (pintype "passive"))
      (node (ref "R15") (pin "2") (pinfunction "2_2") (pintype "passive"))
    )
    (net (code "67") (name "Net-(JP4-Pad2)") (class "Default")
      (node (ref "JP4") (pin "2") (pinfunction "2_2") (pintype "passive"))
      (node (ref "R16") (pin "2") (pinfunction "2_2") (pintype "passive"))
      (node (ref "RN1") (pin "2") (pinfunction "2_2") (pintype "passive"))
    )
    (net (code "68") (name "Net-(JP4-Pad3)") (class "Default")
      (node (ref "JP4") (pin "3") (pinfunction "3_3") (pintype "passive"))
      (node (ref "R17") (pin "2") (pinfunction "2_2") (pintype "passive"))
      (node (ref "RN1") (pin "3") (pinfunction "3_3") (pintype "passive"))
    )
    (net (code "69") (name "Net-(JP4-Pad4)") (class "Default")
      (node (ref "JP4") (pin "4") (pinfunction "4_4") (pintype "passive"))
      (node (ref "R18") (pin "2") (pinfunction "2_2") (pintype "passive"))
      (node (ref "RN1") (pin "4") (pinfunction "4_4") (pintype "passive"))
    )
    (net (code "70") (name "Net-(JP4-Pad5)") (class "Default")
      (node (ref "JP4") (pin "5") (pinfunction "5_5") (pintype "passive"))
      (node (ref "R19") (pin "2") (pinfunction "2_2") (pintype "passive"))
      (node (ref "RN1") (pin "5") (pinfunction "5_5") (pintype "passive"))
    )
    (net (code "71") (name "Net-(JP4-Pad6)") (class "Default")
      (node (ref "JP4") (pin "6") (pinfunction "6_6") (pintype "passive"))
      (node (ref "R20") (pin "2") (pinfunction "2_2") (pintype "passive"))
      (node (ref "RN1") (pin "6") (pinfunction "6_6") (pintype "passive"))
    )
    (net (code "72") (name "Net-(JP4-Pad7)") (class "Default")
      (node (ref "JP4") (pin "7") (pinfunction "7_7") (pintype "passive"))
      (node (ref "R21") (pin "2") (pinfunction "2_2") (pintype "passive"))
      (node (ref "RN1") (pin "7") (pinfunction "7_7") (pintype "passive"))
    )
    (net (code "73") (name "Net-(JP4-Pad8)") (class "Default")
      (node (ref "JP4") (pin "8") (pinfunction "8_8") (pintype "passive"))
      (node (ref "R22") (pin "2") (pinfunction "2_2") (pintype "passive"))
      (node (ref "RN1") (pin "8") (pinfunction "8_8") (pintype "passive"))
    )
    (net (code "74") (name "Net-(JP4-Pad9)") (class "Default")
      (node (ref "JP4") (pin "9") (pinfunction "9_9") (pintype "passive"))
      (node (ref "R23") (pin "2") (pinfunction "2_2") (pintype "passive"))
      (node (ref "RN1") (pin "9") (pinfunction "9_9") (pintype "passive"))
    )
    (net (code "75") (name "Net-(L1-Pad1)") (class "Default")
      (node (ref "L1") (pin "1") (pinfunction "1_1") (pintype "passive"))
      (node (ref "R4") (pin "1") (pinfunction "1_1") (pintype "passive"))
    )
    (net (code "76") (name "Net-(LED1-PadA)") (class "Default")
      (node (ref "LED1") (pin "A") (pinfunction "A_A") (pintype "passive"))
      (node (ref "R1") (pin "1") (pinfunction "1_1") (pintype "passive"))
    )
    (net (code "77") (name "Net-(R2-Pad1)") (class "Default")
      (node (ref "R2") (pin "1") (pinfunction "1_1") (pintype "passive"))
      (node (ref "R3") (pin "1") (pinfunction "1_1") (pintype "passive"))
    )
    (net (code "78") (name "Net-(R13-Pad2)") (class "Default")
      (node (ref "R13") (pin "2") (pinfunction "2_2") (pintype "passive"))
      (node (ref "SPK1") (pin "2") (pinfunction "2_2") (pintype "passive"))
    )
    (net (code "79") (name "VCC_5V") (class "Default")
      (node (ref "*1") (pin "2") (pintype "passive"))
      (node (ref "*2") (pin "12") (pinfunction "SHND_12") (pintype "bidirectional"))
      (node (ref "*2") (pin "13") (pinfunction "PVDD_2_13") (pintype "bidirectional"))
      (node (ref "*2") (pin "4") (pinfunction "PVDD_1_4") (pintype "bidirectional"))
      (node (ref "*2") (pin "5") (pinfunction "MUTE_5") (pintype "bidirectional"))
      (node (ref "*2") (pin "6") (pinfunction "VDD_6") (pintype "bidirectional"))
      (node (ref "C1") (pin "2") (pinfunction "2_2") (pintype "passive"))
      (node (ref "C2") (pin "2") (pinfunction "2_2") (pintype "passive"))
      (node (ref "C3") (pin "1") (pinfunction "1_1") (pintype "passive"))
      (node (ref "C4") (pin "1") (pinfunction "1_1") (pintype "passive"))
      (node (ref "C5") (pin "1") (pinfunction "1_1") (pintype "passive"))
      (node (ref "C8") (pin "1") (pinfunction "1_1") (pintype "passive"))
      (node (ref "IC1") (pin "17") (pinfunction "VDD_17") (pintype "passive"))
      (node (ref "JP1") (pin "2") (pinfunction "2_2") (pintype "passive"))
      (node (ref "R1") (pin "2") (pinfunction "2_2") (pintype "passive"))
      (node (ref "R10") (pin "1") (pinfunction "1_1") (pintype "passive"))
      (node (ref "R14") (pin "2") (pinfunction "2_2") (pintype "passive"))
      (node (ref "R2") (pin "2") (pinfunction "2_2") (pintype "passive"))
      (node (ref "R5") (pin "1") (pinfunction "1_1") (pintype "passive"))
      (node (ref "R6") (pin "1") (pinfunction "1_1") (pintype "passive"))
      (node (ref "R7") (pin "1") (pinfunction "1_1") (pintype "passive"))
      (node (ref "RN1") (pin "1") (pinfunction "1_1") (pintype "passive"))
    )
    (net (code "80") (name "unconnected-(*2-NC-Pad9)") (class "Default")
      (node (ref "*2") (pin "9") (pinfunction "NC_9") (pintype "passive"))
    )
    (net (code "81") (name "unconnected-(*2-PGND_2-Pad15)") (class "Default")
      (node (ref "*2") (pin "15") (pinfunction "PGND_2_15") (pintype "bidirectional"))
    )
    (net (code "82") (name "unconnected-(IC1-OSCI-Pad15)") (class "Default")
      (node (ref "IC1") (pin "15") (pinfunction "OSCI_15") (pintype "passive"))
    )
    (net (code "83") (name "unconnected-(IC1-OSCO-Pad14)") (class "Default")
      (node (ref "IC1") (pin "14") (pinfunction "OSCO_14") (pintype "passive"))
    )
    (net (code "84") (name "unconnected-(IC1-~{IRQ}-Pad18)") (class "Default")
      (node (ref "IC1") (pin "18") (pinfunction "~{IRQ}_18") (pintype "passive"))
    )
    (net (code "85") (name "unconnected-(IC1-~{RD}-Pad10)") (class "Default")
      (node (ref "IC1") (pin "10") (pinfunction "~{RD}_10") (pintype "passive"))
    )
    (net (code "86") (name "unconnected-(VIT1-1-PadVIT1)") (class "Default")
      (node (ref "VIT1") (pin "VIT1") (pinfunction "1_VIT1") (pintype "passive"))
    )
    (net (code "87") (name "unconnected-(VIT2-1-PadVIT1)") (class "Default")
      (node (ref "VIT2") (pin "VIT1") (pinfunction "1_VIT1") (pintype "passive"))
    )
    (net (code "88") (name "unconnected-(VIT3-1-PadVIT1)") (class "Default")
      (node (ref "VIT3") (pin "VIT1") (pinfunction "1_VIT1") (pintype "passive"))
    )
    (net (code "89") (name "unconnected-(VIT4-1-PadVIT1)") (class "Default")
      (node (ref "VIT4") (pin "VIT1") (pinfunction "1_VIT1") (pintype "passive"))
    )
    (net (code "90") (name "unconnected-(VIT5-1-PadVIT1)") (class "Default")
      (node (ref "VIT5") (pin "VIT1") (pinfunction "1_VIT1") (pintype "passive"))
    )
    (net (code "91") (name "unconnected-(VIT6-1-PadVIT1)") (class "Default")
      (node (ref "VIT6") (pin "VIT1") (pinfunction "1_VIT1") (pintype "passive"))
    )
    (net (code "92") (name "unconnected-(VIT7-1-PadVIT1)") (class "Default")
      (node (ref "VIT7") (pin "VIT1") (pinfunction "1_VIT1") (pintype "passive"))
    )
    (net (code "93") (name "unconnected-(VIT8-1-PadVIT1)") (class "Default")
      (node (ref "VIT8") (pin "VIT1") (pinfunction "1_VIT1") (pintype "passive"))
    )
    (net (code "94") (name "unconnected-(VIT9-1-PadVIT1)") (class "Default")
      (node (ref "VIT9") (pin "VIT1") (pinfunction "1_VIT1") (pintype "passive"))
    )
    (net (code "95") (name "unconnected-(VIT10-1-PadVIT1)") (class "Default")
      (node (ref "VIT10") (pin "VIT1") (pinfunction "1_VIT1") (pintype "passive"))
    )
    (net (code "96") (name "unconnected-(VIT11-1-PadVIT1)") (class "Default")
      (node (ref "VIT11") (pin "VIT1") (pinfunction "1_VIT1") (pintype "passive"))
    )
    (net (code "97") (name "unconnected-(VIT12-1-PadVIT1)") (class "Default")
      (node (ref "VIT12") (pin "VIT1") (pinfunction "1_VIT1") (pintype "passive"))
    )
    (net (code "98") (name "unconnected-(VIT13-1-PadVIT1)") (class "Default")
      (node (ref "VIT13") (pin "VIT1") (pinfunction "1_VIT1") (pintype "passive"))
    )
    (net (code "99") (name "unconnected-(VIT14-1-PadVIT1)") (class "Default")
      (node (ref "VIT14") (pin "VIT1") (pinfunction "1_VIT1") (pintype "passive"))
    )
    (net (code "100") (name "unconnected-(VIT15-1-PadVIT1)") (class "Default")
      (node (ref "VIT15") (pin "VIT1") (pinfunction "1_VIT1") (pintype "passive"))
    )
    (net (code "101") (name "unconnected-(VIT16-1-PadVIT1)") (class "Default")
      (node (ref "VIT16") (pin "VIT1") (pinfunction "1_VIT1") (pintype "passive"))
    )
    (net (code "102") (name "unconnected-(VIT17-1-PadVIT1)") (class "Default")
      (node (ref "VIT17") (pin "VIT1") (pinfunction "1_VIT1") (pintype "passive"))
    )
    (net (code "103") (name "unconnected-(VIT18-1-PadVIT1)") (class "Default")
      (node (ref "VIT18") (pin "VIT1") (pinfunction "1_VIT1") (pintype "passive"))
    )
  )
)
